# CYAN_EVSE_Logic_board_v1_1.net
KiCad netlist of a schematic drawn in Altium Designer
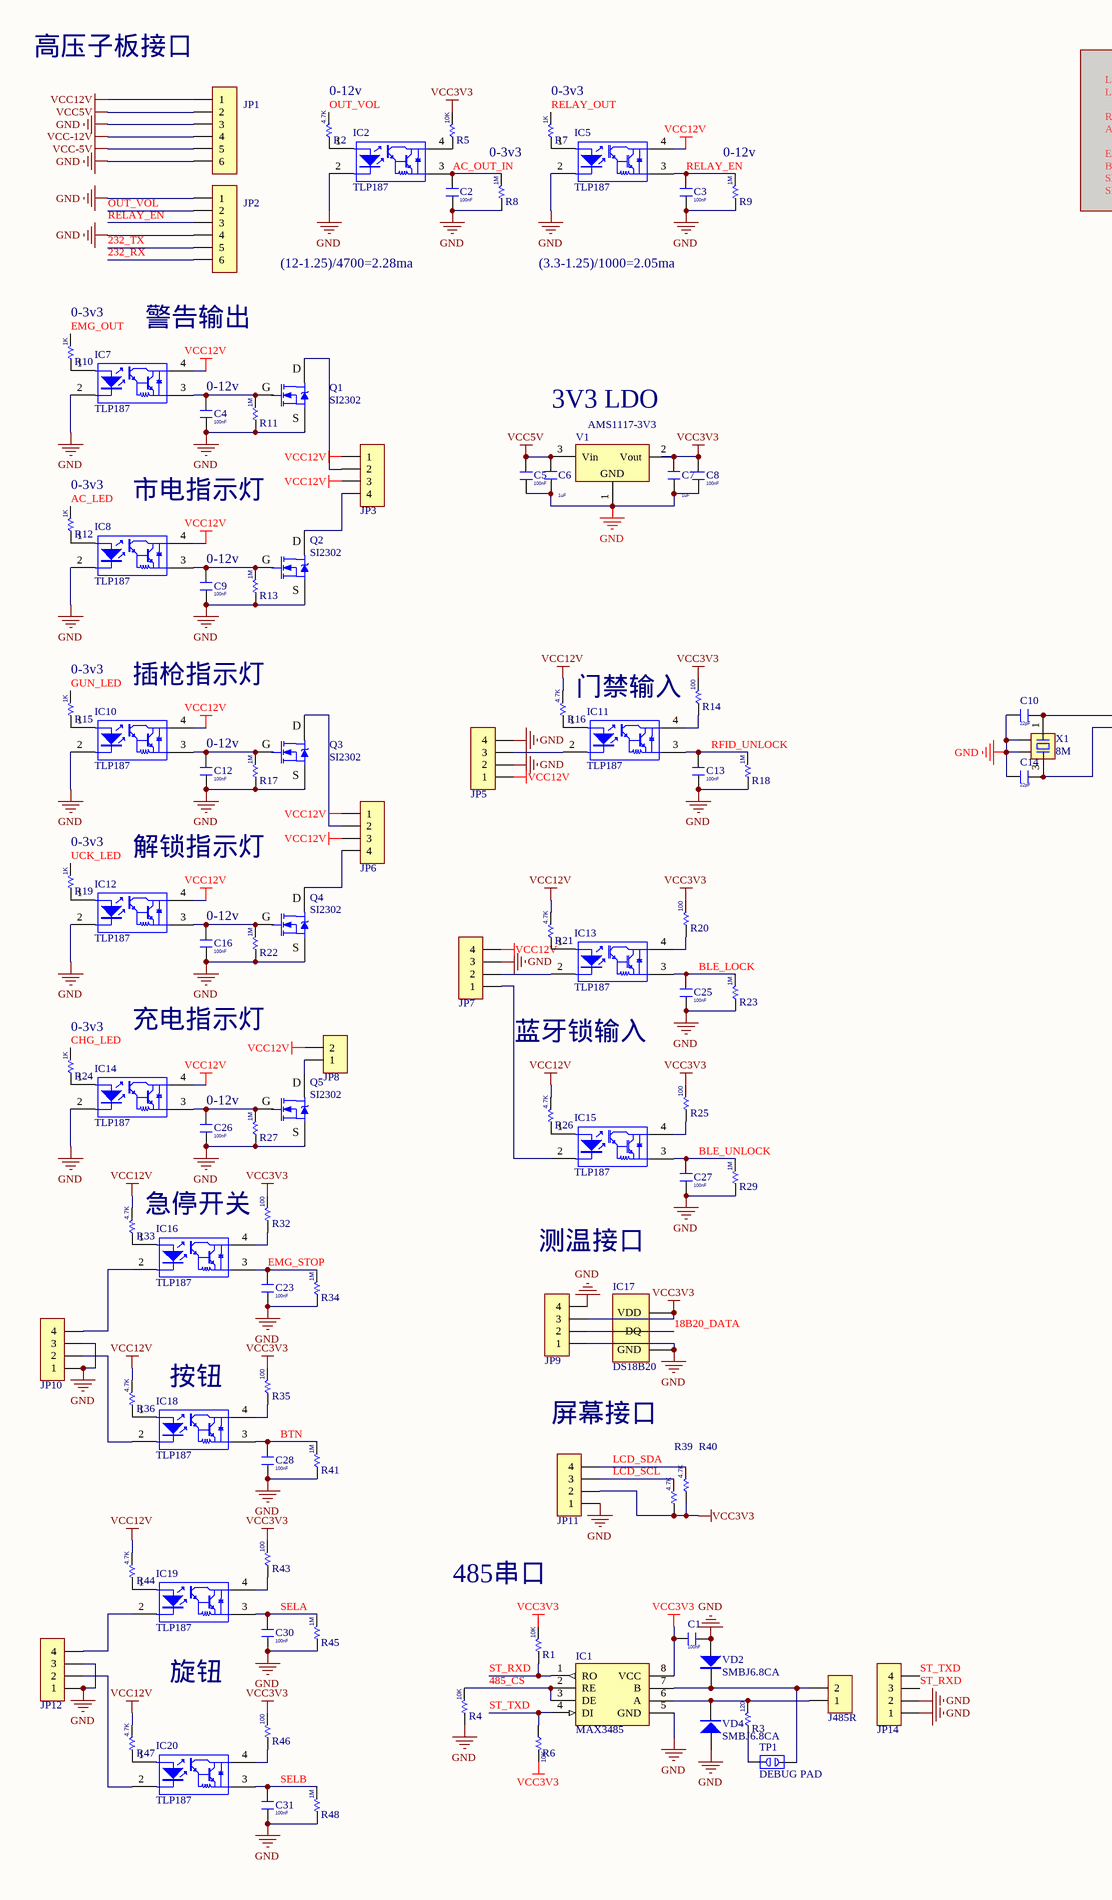
[diagram p0: CYAN_EVSE_Logic_board_v1.1.SchDoc, left]
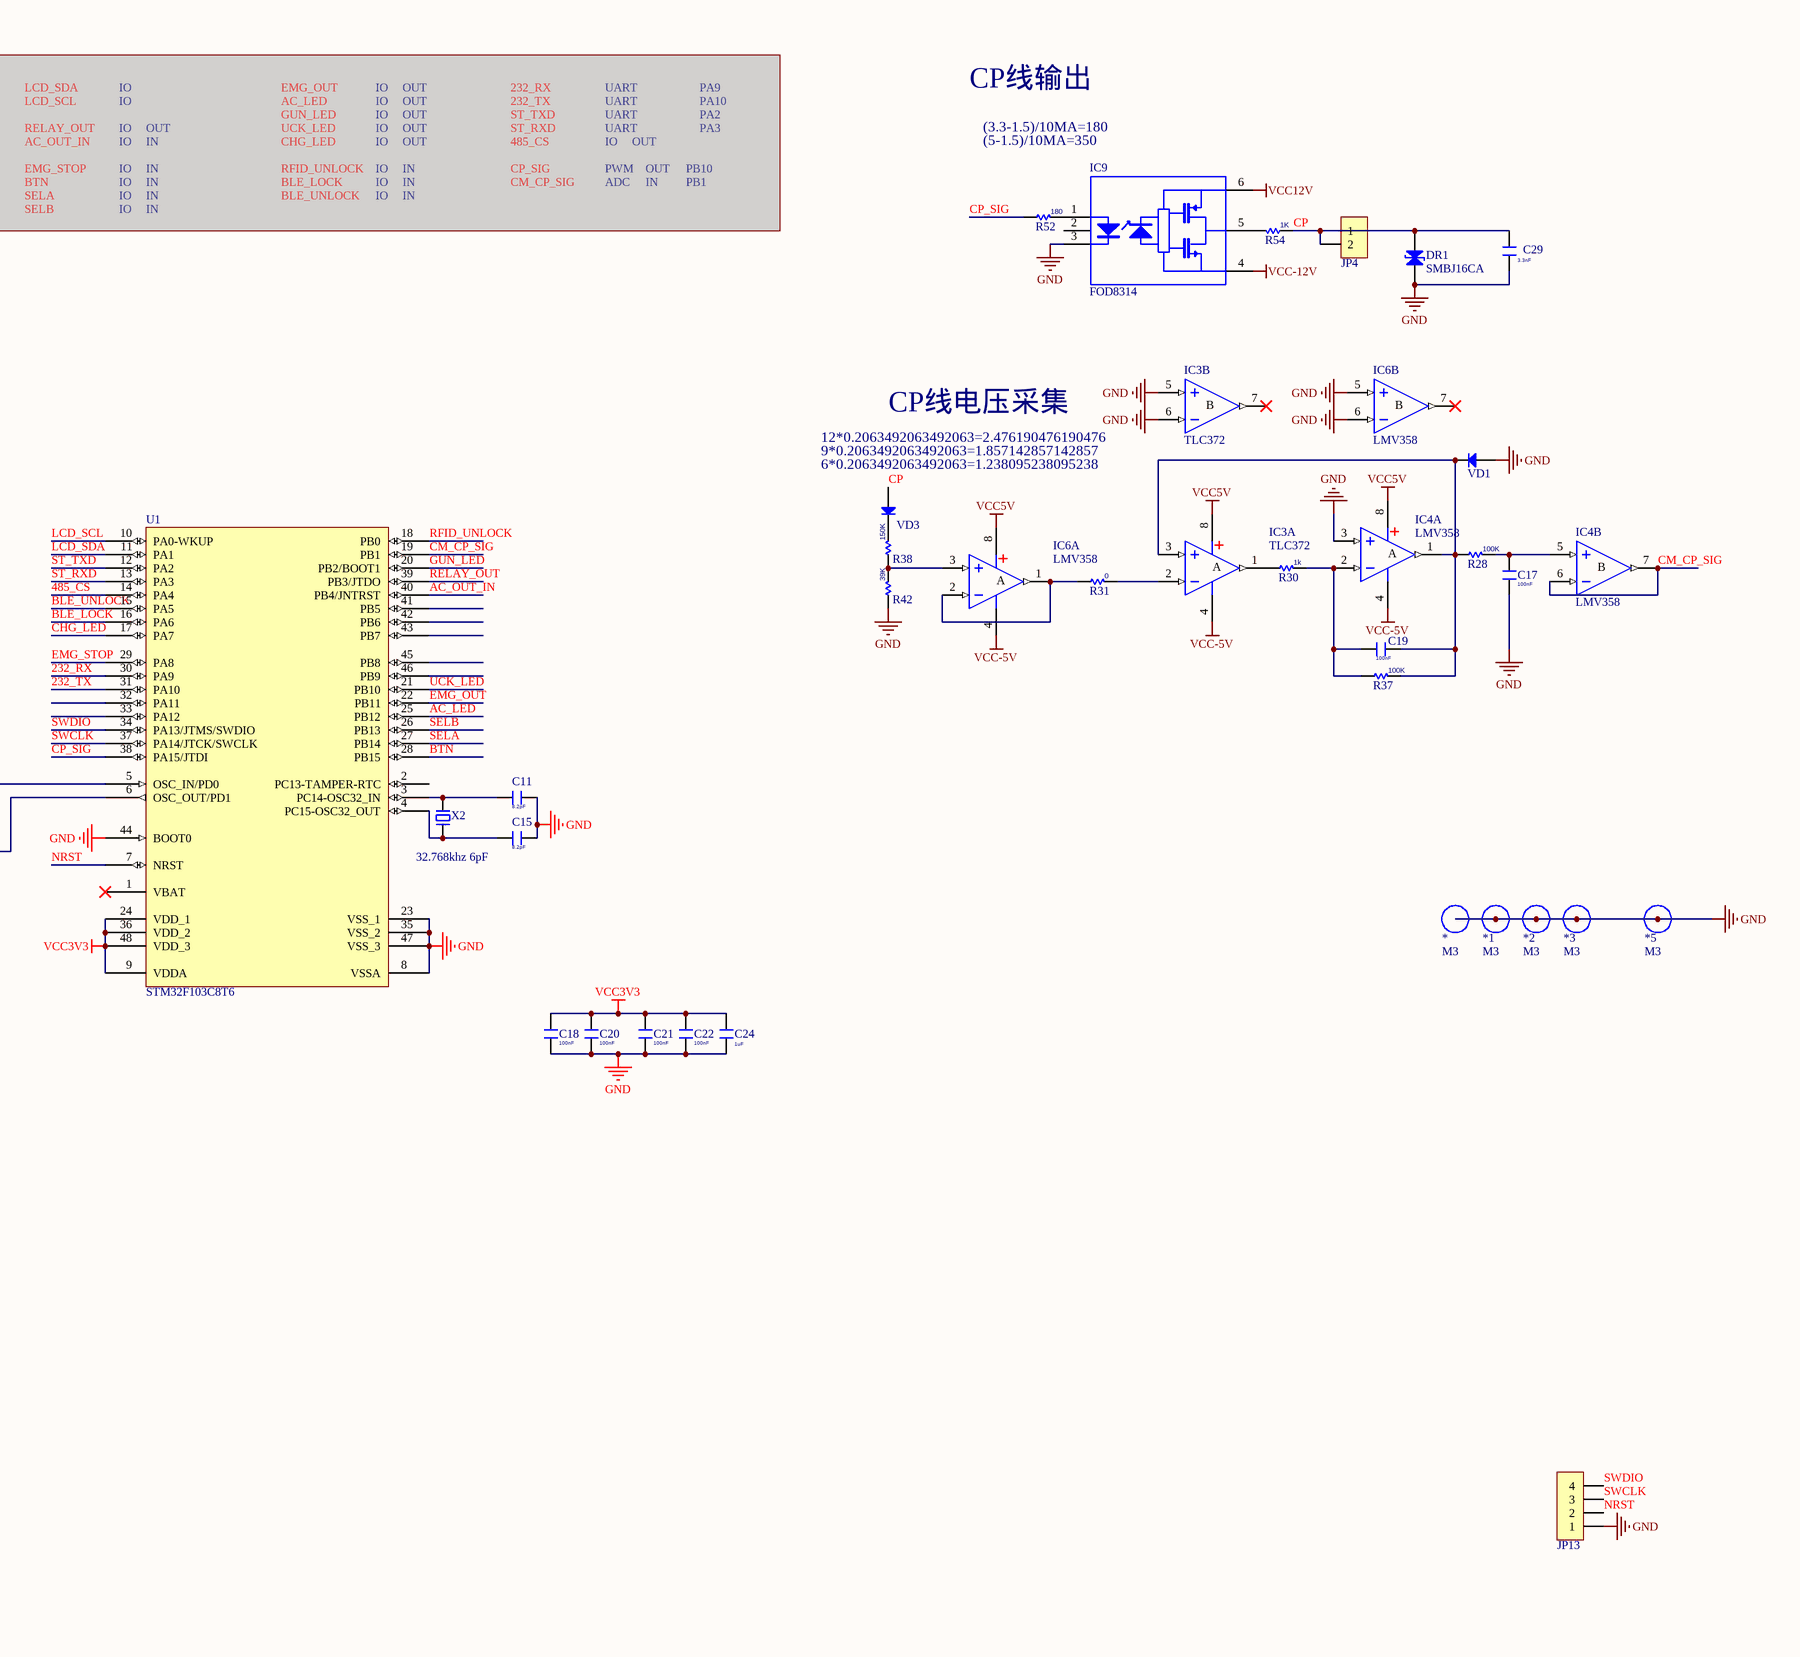
[diagram p1: CYAN_EVSE_Logic_board_v1.1.SchDoc, right]

(export (version "E")
  (design (tool "Eeschema 10.0.6"))
  (components
    (comp (ref "*")
      (value "M3")
      (footprint "M3 125X300")
      (description "铜柱孔")
      (libsource (lib "未分类器件") (part "M3"))
    )
    (comp (ref "*1")
      (value "M3")
      (footprint "M3 125X300")
      (description "铜柱孔")
      (libsource (lib "未分类器件") (part "M3"))
    )
    (comp (ref "*2")
      (value "M3")
      (footprint "M3 125X300")
      (description "铜柱孔")
      (libsource (lib "未分类器件") (part "M3"))
    )
    (comp (ref "*3")
      (value "M3")
      (footprint "M3 125X300")
      (description "铜柱孔")
      (libsource (lib "未分类器件") (part "M3"))
    )
    (comp (ref "*5")
      (value "M3")
      (footprint "M3 125X300")
      (description "铜柱孔")
      (libsource (lib "未分类器件") (part "M3"))
    )
    (comp (ref "C1")
      (value "100nF")
      (footprint "C 0805")
      (description "无极性贴片电容")
      (fields (field (name "VOLTAGE") "20V") (field (name "Comment") "C"))
      (libsource (lib "电阻-电容-电感") (part "C"))
    )
    (comp (ref "C2")
      (value "100nF")
      (footprint "C 0805")
      (description "无极性贴片电容")
      (fields (field (name "VOLTAGE") "20V") (field (name "Comment") "C"))
      (libsource (lib "电阻-电容-电感") (part "C"))
    )
    (comp (ref "C3")
      (value "100nF")
      (footprint "C 0805")
      (description "无极性贴片电容")
      (fields (field (name "VOLTAGE") "20V") (field (name "Comment") "C"))
      (libsource (lib "电阻-电容-电感") (part "C"))
    )
    (comp (ref "C4")
      (value "100nF")
      (footprint "C 0805")
      (description "无极性贴片电容")
      (fields (field (name "VOLTAGE") "20V") (field (name "Comment") "C"))
      (libsource (lib "电阻-电容-电感") (part "C"))
    )
    (comp (ref "C5")
      (value "100nF")
      (footprint "C 0805")
      (description "无极性贴片电容")
      (fields (field (name "VOLTAGE") "20V") (field (name "Comment") "C"))
      (libsource (lib "电阻-电容-电感") (part "C"))
    )
    (comp (ref "C6")
      (value "1uF")
      (footprint "C 0805")
      (description "无极性贴片电容")
      (fields (field (name "Comment") "C"))
      (libsource (lib "电阻-电容-电感") (part "C"))
    )
    (comp (ref "C7")
      (value "1uF")
      (footprint "C 0805")
      (description "无极性贴片电容")
      (fields (field (name "Comment") "C"))
      (libsource (lib "电阻-电容-电感") (part "C"))
    )
    (comp (ref "C8")
      (value "100nF")
      (footprint "C 0805")
      (description "无极性贴片电容")
      (fields (field (name "VOLTAGE") "20V") (field (name "Comment") "C"))
      (libsource (lib "电阻-电容-电感") (part "C"))
    )
    (comp (ref "C9")
      (value "100nF")
      (footprint "C 0805")
      (description "无极性贴片电容")
      (fields (field (name "VOLTAGE") "20V") (field (name "Comment") "C"))
      (libsource (lib "电阻-电容-电感") (part "C"))
    )
    (comp (ref "C10")
      (value "22pF")
      (footprint "C 0805")
      (description "无极性贴片电容")
      (fields (field (name "VOLTAGE") "20V") (field (name "Comment") "C"))
      (libsource (lib "电阻-电容-电感") (part "C"))
    )
    (comp (ref "C11")
      (value "8.2pF")
      (footprint "C 0805")
      (description "无极性贴片电容")
      (fields (field (name "VOLTAGE") "20V") (field (name "Comment") "C"))
      (libsource (lib "电阻-电容-电感") (part "C"))
    )
    (comp (ref "C12")
      (value "100nF")
      (footprint "C 0805")
      (description "无极性贴片电容")
      (fields (field (name "VOLTAGE") "20V") (field (name "Comment") "C"))
      (libsource (lib "电阻-电容-电感") (part "C"))
    )
    (comp (ref "C13")
      (value "100nF")
      (footprint "C 0805")
      (description "无极性贴片电容")
      (fields (field (name "VOLTAGE") "20V") (field (name "Comment") "C"))
      (libsource (lib "电阻-电容-电感") (part "C"))
    )
    (comp (ref "C14")
      (value "22pF")
      (footprint "C 0805")
      (description "无极性贴片电容")
      (fields (field (name "VOLTAGE") "20V") (field (name "Comment") "C"))
      (libsource (lib "电阻-电容-电感") (part "C"))
    )
    (comp (ref "C15")
      (value "8.2pF")
      (footprint "C 0805")
      (description "无极性贴片电容")
      (fields (field (name "VOLTAGE") "20V") (field (name "Comment") "C"))
      (libsource (lib "电阻-电容-电感") (part "C"))
    )
    (comp (ref "C16")
      (value "100nF")
      (footprint "C 0805")
      (description "无极性贴片电容")
      (fields (field (name "VOLTAGE") "20V") (field (name "Comment") "C"))
      (libsource (lib "电阻-电容-电感") (part "C"))
    )
    (comp (ref "C17")
      (value "100nF")
      (footprint "C 0805")
      (description "无极性贴片电容")
      (fields (field (name "VOLTAGE") "20V") (field (name "Comment") "C"))
      (libsource (lib "电阻-电容-电感") (part "C"))
    )
    (comp (ref "C18")
      (value "100nF")
      (footprint "C 0805")
      (description "无极性贴片电容")
      (fields (field (name "VOLTAGE") "20V") (field (name "Comment") "C"))
      (libsource (lib "电阻-电容-电感") (part "C"))
    )
    (comp (ref "C19")
      (value "100nF")
      (footprint "C 0805")
      (description "无极性贴片电容")
      (fields (field (name "VOLTAGE") "20V") (field (name "Comment") "C"))
      (libsource (lib "电阻-电容-电感") (part "C"))
    )
    (comp (ref "C20")
      (value "100nF")
      (footprint "C 0805")
      (description "无极性贴片电容")
      (fields (field (name "VOLTAGE") "20V") (field (name "Comment") "C"))
      (libsource (lib "电阻-电容-电感") (part "C"))
    )
    (comp (ref "C21")
      (value "100nF")
      (footprint "C 0805")
      (description "无极性贴片电容")
      (fields (field (name "VOLTAGE") "20V") (field (name "Comment") "C"))
      (libsource (lib "电阻-电容-电感") (part "C"))
    )
    (comp (ref "C22")
      (value "100nF")
      (footprint "C 0805")
      (description "无极性贴片电容")
      (fields (field (name "VOLTAGE") "20V") (field (name "Comment") "C"))
      (libsource (lib "电阻-电容-电感") (part "C"))
    )
    (comp (ref "C23")
      (value "100nF")
      (footprint "C 0805")
      (description "无极性贴片电容")
      (fields (field (name "VOLTAGE") "20V") (field (name "Comment") "C"))
      (libsource (lib "电阻-电容-电感") (part "C"))
    )
    (comp (ref "C24")
      (value "1uF")
      (footprint "C 0805")
      (description "无极性贴片电容")
      (fields (field (name "Comment") "C"))
      (libsource (lib "电阻-电容-电感") (part "C"))
    )
    (comp (ref "C25")
      (value "100nF")
      (footprint "C 0805")
      (description "无极性贴片电容")
      (fields (field (name "VOLTAGE") "20V") (field (name "Comment") "C"))
      (libsource (lib "电阻-电容-电感") (part "C"))
    )
    (comp (ref "C26")
      (value "100nF")
      (footprint "C 0805")
      (description "无极性贴片电容")
      (fields (field (name "VOLTAGE") "20V") (field (name "Comment") "C"))
      (libsource (lib "电阻-电容-电感") (part "C"))
    )
    (comp (ref "C27")
      (value "100nF")
      (footprint "C 0805")
      (description "无极性贴片电容")
      (fields (field (name "VOLTAGE") "20V") (field (name "Comment") "C"))
      (libsource (lib "电阻-电容-电感") (part "C"))
    )
    (comp (ref "C28")
      (value "100nF")
      (footprint "C 0805")
      (description "无极性贴片电容")
      (fields (field (name "VOLTAGE") "20V") (field (name "Comment") "C"))
      (libsource (lib "电阻-电容-电感") (part "C"))
    )
    (comp (ref "C29")
      (value "3.3nF")
      (footprint "C 1206")
      (description "无极性贴片电容")
      (fields (field (name "VOLTAGE") "50V") (field (name "Comment") "C"))
      (libsource (lib "电阻-电容-电感") (part "C"))
    )
    (comp (ref "C30")
      (value "100nF")
      (footprint "C 0805")
      (description "无极性贴片电容")
      (fields (field (name "VOLTAGE") "20V") (field (name "Comment") "C"))
      (libsource (lib "电阻-电容-电感") (part "C"))
    )
    (comp (ref "C31")
      (value "100nF")
      (footprint "C 0805")
      (description "无极性贴片电容")
      (fields (field (name "VOLTAGE") "20V") (field (name "Comment") "C"))
      (libsource (lib "电阻-电容-电感") (part "C"))
    )
    (comp (ref "DR1")
      (value "SMBJ16CA")
      (footprint "SMB")
      (description "瞬态电压抑制二极管")
      (libsource (lib "二极管-整流桥") (part "DR"))
    )
    (comp (ref "IC1")
      (value "MAX3485")
      (footprint "SOP8_N")
      (description "RS485总线收发芯片")
      (libsource (lib "IC芯片") (part "MAX487"))
    )
    (comp (ref "IC2")
      (value "TLP187")
      (footprint "SOP6_4.6MM_W1.27_4PIN_N")
      (description "达林顿输出光耦")
      (libsource (lib "传感元件") (part "TLP187"))
    )
    (comp (ref "IC3")
      (value "TLC372")
      (footprint "SOP8_N")
      (description "双路电压比较,MOS下臂输出")
      (libsource (lib "IC芯片") (part "TLC372"))
    )
    (comp (ref "IC4")
      (value "LMV358")
      (footprint "SOP8_N")
      (description "双路运放")
      (libsource (lib "IC芯片") (part "LM358"))
    )
    (comp (ref "IC5")
      (value "TLP187")
      (footprint "SOP6_4.6MM_W1.27_4PIN_N")
      (description "达林顿输出光耦")
      (libsource (lib "传感元件") (part "TLP187"))
    )
    (comp (ref "IC6")
      (value "LMV358")
      (footprint "SOP8_N")
      (description "双路运放")
      (libsource (lib "IC芯片") (part "LM358"))
    )
    (comp (ref "IC7")
      (value "TLP187")
      (footprint "SOP6_4.6MM_W1.27_4PIN_N")
      (description "达林顿输出光耦")
      (libsource (lib "传感元件") (part "TLP187"))
    )
    (comp (ref "IC8")
      (value "TLP187")
      (footprint "SOP6_4.6MM_W1.27_4PIN_N")
      (description "达林顿输出光耦")
      (libsource (lib "传感元件") (part "TLP187"))
    )
    (comp (ref "IC9")
      (value "FOD8314")
      (footprint "SOP6_7MM_WIDE_LEAD_N")
      (description "MOSFET/IGBT 驱动光耦，15-30v 1a")
      (libsource (lib "传感元件") (part "FOD8314"))
    )
    (comp (ref "IC10")
      (value "TLP187")
      (footprint "SOP6_4.6MM_W1.27_4PIN_N")
      (description "达林顿输出光耦")
      (libsource (lib "传感元件") (part "TLP187"))
    )
    (comp (ref "IC11")
      (value "TLP187")
      (footprint "SOP6_4.6MM_W1.27_4PIN_N")
      (description "达林顿输出光耦")
      (libsource (lib "传感元件") (part "TLP187"))
    )
    (comp (ref "IC12")
      (value "TLP187")
      (footprint "SOP6_4.6MM_W1.27_4PIN_N")
      (description "达林顿输出光耦")
      (libsource (lib "传感元件") (part "TLP187"))
    )
    (comp (ref "IC13")
      (value "TLP187")
      (footprint "SOP6_4.6MM_W1.27_4PIN_N")
      (description "达林顿输出光耦")
      (libsource (lib "传感元件") (part "TLP187"))
    )
    (comp (ref "IC14")
      (value "TLP187")
      (footprint "SOP6_4.6MM_W1.27_4PIN_N")
      (description "达林顿输出光耦")
      (libsource (lib "传感元件") (part "TLP187"))
    )
    (comp (ref "IC15")
      (value "TLP187")
      (footprint "SOP6_4.6MM_W1.27_4PIN_N")
      (description "达林顿输出光耦")
      (libsource (lib "传感元件") (part "TLP187"))
    )
    (comp (ref "IC16")
      (value "TLP187")
      (footprint "SOP6_4.6MM_W1.27_4PIN_N")
      (description "达林顿输出光耦")
      (libsource (lib "传感元件") (part "TLP187"))
    )
    (comp (ref "IC17")
      (value "DS18B20")
      (footprint "TO92A")
      (description "数字温度计")
      (libsource (lib "IC芯片") (part "DS18B20"))
    )
    (comp (ref "IC18")
      (value "TLP187")
      (footprint "SOP6_4.6MM_W1.27_4PIN_N")
      (description "达林顿输出光耦")
      (libsource (lib "传感元件") (part "TLP187"))
    )
    (comp (ref "IC19")
      (value "TLP187")
      (footprint "SOP6_4.6MM_W1.27_4PIN_N")
      (description "达林顿输出光耦")
      (libsource (lib "传感元件") (part "TLP187"))
    )
    (comp (ref "IC20")
      (value "TLP187")
      (footprint "SOP6_4.6MM_W1.27_4PIN_N")
      (description "达林顿输出光耦")
      (libsource (lib "传感元件") (part "TLP187"))
    )
    (comp (ref "J485R")
      (value "HDR-1X2")
      (footprint "MC 1,5/ 2-G-3,81")
      (description "2P接插件")
      (libsource (lib "接插件") (part "Header 2"))
    )
    (comp (ref "JP1")
      (value "HDR-1X6")
      (footprint "XH2.54-6P")
      (description "6P接插件")
      (libsource (lib "接插件") (part "Header 6"))
    )
    (comp (ref "JP2")
      (value "HDR-1X6")
      (footprint "XH2.54-6P")
      (description "6P接插件")
      (libsource (lib "接插件") (part "Header 6"))
    )
    (comp (ref "JP3")
      (value "HDR-1X4")
      (footprint "MC 1,5/ 4-G-3,81")
      (description "4P接插件")
      (libsource (lib "") (part "Header 4_1"))
    )
    (comp (ref "JP4")
      (value "HDR-1X2")
      (footprint "MC 1,5/ 2-G-3,81")
      (description "2P接插件")
      (libsource (lib "") (part "Header 2_1"))
    )
    (comp (ref "JP5")
      (value "HDR-1X4")
      (footprint "MC 1,5/ 4-G-3,81")
      (description "4P接插件")
      (libsource (lib "接插件") (part "Header 4"))
    )
    (comp (ref "JP6")
      (value "HDR-1X4")
      (footprint "MC 1,5/ 4-G-3,81")
      (description "4P接插件")
      (libsource (lib "") (part "Header 4_1"))
    )
    (comp (ref "JP7")
      (value "HDR-1X4")
      (footprint "MC 1,5/ 4-G-3,81")
      (description "4P接插件")
      (libsource (lib "接插件") (part "Header 4"))
    )
    (comp (ref "JP8")
      (value "HDR-1X2")
      (footprint "MC 1,5/ 2-G-3,81")
      (description "2P接插件")
      (libsource (lib "接插件") (part "Header 2"))
    )
    (comp (ref "JP9")
      (value "HDR-1X4")
      (footprint "MC 1,5/ 4-G-3,81")
      (description "4P接插件")
      (libsource (lib "接插件") (part "Header 4"))
    )
    (comp (ref "JP10")
      (value "HDR-1X4")
      (footprint "MC 1,5/ 4-G-3,81")
      (description "4P接插件")
      (libsource (lib "接插件") (part "Header 4"))
    )
    (comp (ref "JP11")
      (value "HDR-1X4")
      (footprint "XH2.54-4P")
      (description "4P接插件")
      (libsource (lib "接插件") (part "Header 4"))
    )
    (comp (ref "JP12")
      (value "HDR-1X4")
      (footprint "MC 1,5/ 4-G-3,81")
      (description "4P接插件")
      (libsource (lib "接插件") (part "Header 4"))
    )
    (comp (ref "JP13")
      (value "HDR-1X4")
      (footprint "HDR-1X4")
      (description "4P接插件")
      (libsource (lib "接插件") (part "Header 4"))
    )
    (comp (ref "JP14")
      (value "HDR-1X4")
      (footprint "HDR-1X4")
      (description "4P接插件")
      (libsource (lib "接插件") (part "Header 4"))
    )
    (comp (ref "Q1")
      (value "SI2302")
      (footprint "SOT23-3N")
      (description "N沟道场效应管")
      (libsource (lib "场效应管-可控硅") (part "SI2302"))
    )
    (comp (ref "Q2")
      (value "SI2302")
      (footprint "SOT23-3N")
      (description "N沟道场效应管")
      (libsource (lib "场效应管-可控硅") (part "SI2302"))
    )
    (comp (ref "Q3")
      (value "SI2302")
      (footprint "SOT23-3N")
      (description "N沟道场效应管")
      (libsource (lib "场效应管-可控硅") (part "SI2302"))
    )
    (comp (ref "Q4")
      (value "SI2302")
      (footprint "SOT23-3N")
      (description "N沟道场效应管")
      (libsource (lib "场效应管-可控硅") (part "SI2302"))
    )
    (comp (ref "Q5")
      (value "SI2302")
      (footprint "SOT23-3N")
      (description "N沟道场效应管")
      (libsource (lib "场效应管-可控硅") (part "SI2302"))
    )
    (comp (ref "R1")
      (value "10K")
      (footprint "R 0805")
      (description "贴片电阻")
      (fields (field (name "Comment") "R"))
      (libsource (lib "电阻-电容-电感") (part "R"))
    )
    (comp (ref "R2")
      (value "4.7K")
      (footprint "R 0805")
      (description "贴片电阻")
      (fields (field (name "Comment") "R"))
      (libsource (lib "电阻-电容-电感") (part "R"))
    )
    (comp (ref "R3")
      (value "120")
      (footprint "R 1206")
      (description "贴片电阻")
      (fields (field (name "Comment") "R"))
      (libsource (lib "电阻-电容-电感") (part "R"))
    )
    (comp (ref "R4")
      (value "10K")
      (footprint "R 0805")
      (description "贴片电阻")
      (fields (field (name "Comment") "R"))
      (libsource (lib "电阻-电容-电感") (part "R"))
    )
    (comp (ref "R5")
      (value "10K")
      (footprint "R 0805")
      (description "贴片电阻")
      (fields (field (name "Comment") "R"))
      (libsource (lib "电阻-电容-电感") (part "R"))
    )
    (comp (ref "R6")
      (value "10K")
      (footprint "R 0805")
      (description "贴片电阻")
      (fields (field (name "Comment") "R"))
      (libsource (lib "电阻-电容-电感") (part "R"))
    )
    (comp (ref "R7")
      (value "1K")
      (footprint "R 0805")
      (description "贴片电阻")
      (fields (field (name "Comment") "R"))
      (libsource (lib "电阻-电容-电感") (part "R"))
    )
    (comp (ref "R8")
      (value "1M")
      (footprint "R 0805")
      (description "贴片电阻")
      (fields (field (name "Comment") "R"))
      (libsource (lib "电阻-电容-电感") (part "R"))
    )
    (comp (ref "R9")
      (value "1M")
      (footprint "R 0805")
      (description "贴片电阻")
      (fields (field (name "Comment") "R"))
      (libsource (lib "电阻-电容-电感") (part "R"))
    )
    (comp (ref "R10")
      (value "1K")
      (footprint "R 0805")
      (description "贴片电阻")
      (fields (field (name "Comment") "R"))
      (libsource (lib "电阻-电容-电感") (part "R"))
    )
    (comp (ref "R11")
      (value "1M")
      (footprint "R 0805")
      (description "贴片电阻")
      (fields (field (name "Comment") "R"))
      (libsource (lib "电阻-电容-电感") (part "R"))
    )
    (comp (ref "R12")
      (value "1K")
      (footprint "R 0805")
      (description "贴片电阻")
      (fields (field (name "Comment") "R"))
      (libsource (lib "电阻-电容-电感") (part "R"))
    )
    (comp (ref "R13")
      (value "1M")
      (footprint "R 0805")
      (description "贴片电阻")
      (fields (field (name "Comment") "R"))
      (libsource (lib "电阻-电容-电感") (part "R"))
    )
    (comp (ref "R14")
      (value "100")
      (footprint "R 0805")
      (description "贴片电阻")
      (fields (field (name "Comment") "R"))
      (libsource (lib "电阻-电容-电感") (part "R"))
    )
    (comp (ref "R15")
      (value "1K")
      (footprint "R 0805")
      (description "贴片电阻")
      (fields (field (name "Comment") "R"))
      (libsource (lib "电阻-电容-电感") (part "R"))
    )
    (comp (ref "R16")
      (value "4.7K")
      (footprint "R 0805")
      (description "贴片电阻")
      (fields (field (name "Comment") "R"))
      (libsource (lib "电阻-电容-电感") (part "R"))
    )
    (comp (ref "R17")
      (value "1M")
      (footprint "R 0805")
      (description "贴片电阻")
      (fields (field (name "Comment") "R"))
      (libsource (lib "电阻-电容-电感") (part "R"))
    )
    (comp (ref "R18")
      (value "1M")
      (footprint "R 0805")
      (description "贴片电阻")
      (fields (field (name "Comment") "R"))
      (libsource (lib "电阻-电容-电感") (part "R"))
    )
    (comp (ref "R19")
      (value "1K")
      (footprint "R 0805")
      (description "贴片电阻")
      (fields (field (name "Comment") "R"))
      (libsource (lib "电阻-电容-电感") (part "R"))
    )
    (comp (ref "R20")
      (value "100")
      (footprint "R 0805")
      (description "贴片电阻")
      (fields (field (name "Comment") "R"))
      (libsource (lib "电阻-电容-电感") (part "R"))
    )
    (comp (ref "R21")
      (value "4.7K")
      (footprint "R 0805")
      (description "贴片电阻")
      (fields (field (name "Comment") "R"))
      (libsource (lib "电阻-电容-电感") (part "R"))
    )
    (comp (ref "R22")
      (value "1M")
      (footprint "R 0805")
      (description "贴片电阻")
      (fields (field (name "Comment") "R"))
      (libsource (lib "电阻-电容-电感") (part "R"))
    )
    (comp (ref "R23")
      (value "1M")
      (footprint "R 0805")
      (description "贴片电阻")
      (fields (field (name "Comment") "R"))
      (libsource (lib "电阻-电容-电感") (part "R"))
    )
    (comp (ref "R24")
      (value "1K")
      (footprint "R 0805")
      (description "贴片电阻")
      (fields (field (name "Comment") "R"))
      (libsource (lib "电阻-电容-电感") (part "R"))
    )
    (comp (ref "R25")
      (value "100")
      (footprint "R 0805")
      (description "贴片电阻")
      (fields (field (name "Comment") "R"))
      (libsource (lib "电阻-电容-电感") (part "R"))
    )
    (comp (ref "R26")
      (value "4.7K")
      (footprint "R 0805")
      (description "贴片电阻")
      (fields (field (name "Comment") "R"))
      (libsource (lib "电阻-电容-电感") (part "R"))
    )
    (comp (ref "R27")
      (value "1M")
      (footprint "R 0805")
      (description "贴片电阻")
      (fields (field (name "Comment") "R"))
      (libsource (lib "电阻-电容-电感") (part "R"))
    )
    (comp (ref "R28")
      (value "100K")
      (footprint "R 0805")
      (description "贴片电阻")
      (fields (field (name "Comment") "R"))
      (libsource (lib "电阻-电容-电感") (part "R"))
    )
    (comp (ref "R29")
      (value "1M")
      (footprint "R 0805")
      (description "贴片电阻")
      (fields (field (name "Comment") "R"))
      (libsource (lib "电阻-电容-电感") (part "R"))
    )
    (comp (ref "R30")
      (value "1k")
      (footprint "R 0805")
      (description "贴片电阻")
      (fields (field (name "Comment") "R"))
      (libsource (lib "电阻-电容-电感") (part "R"))
    )
    (comp (ref "R31")
      (value "0")
      (footprint "R 0805")
      (description "贴片电阻")
      (fields (field (name "Comment") "R"))
      (libsource (lib "电阻-电容-电感") (part "R"))
    )
    (comp (ref "R32")
      (value "100")
      (footprint "R 0805")
      (description "贴片电阻")
      (fields (field (name "Comment") "R"))
      (libsource (lib "电阻-电容-电感") (part "R"))
    )
    (comp (ref "R33")
      (value "4.7K")
      (footprint "R 0805")
      (description "贴片电阻")
      (fields (field (name "Comment") "R"))
      (libsource (lib "电阻-电容-电感") (part "R"))
    )
    (comp (ref "R34")
      (value "1M")
      (footprint "R 0805")
      (description "贴片电阻")
      (fields (field (name "Comment") "R"))
      (libsource (lib "电阻-电容-电感") (part "R"))
    )
    (comp (ref "R35")
      (value "100")
      (footprint "R 0805")
      (description "贴片电阻")
      (fields (field (name "Comment") "R"))
      (libsource (lib "电阻-电容-电感") (part "R"))
    )
    (comp (ref "R36")
      (value "4.7K")
      (footprint "R 0805")
      (description "贴片电阻")
      (fields (field (name "Comment") "R"))
      (libsource (lib "电阻-电容-电感") (part "R"))
    )
    (comp (ref "R37")
      (value "100K")
      (footprint "R 0805")
      (description "贴片电阻")
      (fields (field (name "Comment") "R"))
      (libsource (lib "电阻-电容-电感") (part "R"))
    )
    (comp (ref "R38")
      (value "150K")
      (footprint "R 0805")
      (description "贴片电阻")
      (fields (field (name "Comment") "R"))
      (libsource (lib "电阻-电容-电感") (part "R"))
    )
    (comp (ref "R39")
      (value "4.7K")
      (footprint "R 0805")
      (description "贴片电阻")
      (fields (field (name "Comment") "R"))
      (libsource (lib "电阻-电容-电感") (part "R"))
    )
    (comp (ref "R40")
      (value "4.7K")
      (footprint "R 0805")
      (description "贴片电阻")
      (fields (field (name "Comment") "R"))
      (libsource (lib "电阻-电容-电感") (part "R"))
    )
    (comp (ref "R41")
      (value "1M")
      (footprint "R 0805")
      (description "贴片电阻")
      (fields (field (name "Comment") "R"))
      (libsource (lib "电阻-电容-电感") (part "R"))
    )
    (comp (ref "R42")
      (value "39K")
      (footprint "R 0805")
      (description "贴片电阻")
      (fields (field (name "Comment") "R"))
      (libsource (lib "电阻-电容-电感") (part "R"))
    )
    (comp (ref "R43")
      (value "100")
      (footprint "R 0805")
      (description "贴片电阻")
      (fields (field (name "Comment") "R"))
      (libsource (lib "电阻-电容-电感") (part "R"))
    )
    (comp (ref "R44")
      (value "4.7K")
      (footprint "R 0805")
      (description "贴片电阻")
      (fields (field (name "Comment") "R"))
      (libsource (lib "电阻-电容-电感") (part "R"))
    )
    (comp (ref "R45")
      (value "1M")
      (footprint "R 0805")
      (description "贴片电阻")
      (fields (field (name "Comment") "R"))
      (libsource (lib "电阻-电容-电感") (part "R"))
    )
    (comp (ref "R46")
      (value "100")
      (footprint "R 0805")
      (description "贴片电阻")
      (fields (field (name "Comment") "R"))
      (libsource (lib "电阻-电容-电感") (part "R"))
    )
    (comp (ref "R47")
      (value "4.7K")
      (footprint "R 0805")
      (description "贴片电阻")
      (fields (field (name "Comment") "R"))
      (libsource (lib "电阻-电容-电感") (part "R"))
    )
    (comp (ref "R48")
      (value "1M")
      (footprint "R 0805")
      (description "贴片电阻")
      (fields (field (name "Comment") "R"))
      (libsource (lib "电阻-电容-电感") (part "R"))
    )
    (comp (ref "R52")
      (value "180")
      (footprint "R 0805")
      (description "贴片电阻")
      (fields (field (name "Comment") "R"))
      (libsource (lib "电阻-电容-电感") (part "R"))
    )
    (comp (ref "R54")
      (value "1K")
      (footprint "R 1206")
      (description "贴片电阻")
      (fields (field (name "Comment") "R"))
      (libsource (lib "电阻-电容-电感") (part "R"))
    )
    (comp (ref "TP1")
      (value "DEBUG PAD")
      (footprint "DEBUG PAD2")
      (description "调试断点焊盘")
      (libsource (lib "未分类器件") (part "DEBUG"))
    )
    (comp (ref "U1")
      (value "STM32F103C8T6")
      (footprint "LQFP48 7X7_M")
      (description "Flaah:64/RAM:20/IO:36")
      (libsource (lib "STM32系列单片机") (part "STM32F103C8T6"))
    )
    (comp (ref "V1")
      (value "AMS1117-3V3")
      (footprint "SOT223_L")
      (description "三端稳压芯片")
      (libsource (lib "IC芯片") (part "AMS1117"))
    )
    (comp (ref "VD1")
      (value "1N4148")
      (footprint "SOD-323")
      (description "高速开关二极管")
      (libsource (lib "二极管-整流桥") (part "1N4148"))
    )
    (comp (ref "VD2")
      (value "SMBJ6.8CA")
      (footprint "SMB")
      (description "肖特基二极管")
      (libsource (lib "二极管-整流桥") (part "SS14"))
    )
    (comp (ref "VD3")
      (value "1N4148")
      (footprint "SOD-323")
      (description "高速开关二极管")
      (libsource (lib "二极管-整流桥") (part "1N4148"))
    )
    (comp (ref "VD4")
      (value "SMBJ6.8CA")
      (footprint "SMB")
      (description "肖特基二极管")
      (libsource (lib "二极管-整流桥") (part "SS14"))
    )
    (comp (ref "X1")
      (value "8M")
      (footprint "XTAL-3225")
      (description "4脚晶振")
      (libsource (lib "保险丝-晶振") (part "XTAL-4"))
    )
    (comp (ref "X2")
      (value "32.768khz 6pF")
      (footprint "XTAL-3215")
      (description "2脚晶振")
      (libsource (lib "保险丝-晶振") (part "XTAL-2"))
    )
  )
  (nets
    (net (code "1") (name "/18B20_DATA") (class "Default")
      (node (ref "IC17") (pin "2") (pinfunction "DQ_2") (pintype "passive"))
      (node (ref "JP9") (pin "2") (pinfunction "2_2") (pintype "passive"))
    )
    (net (code "2") (name "/232_RX") (class "Default")
      (node (ref "JP2") (pin "6") (pinfunction "6_6") (pintype "passive"))
      (node (ref "U1") (pin "30") (pinfunction "PA9_30") (pintype "bidirectional"))
    )
    (net (code "3") (name "/232_TX") (class "Default")
      (node (ref "JP2") (pin "5") (pinfunction "5_5") (pintype "passive"))
      (node (ref "U1") (pin "31") (pinfunction "PA10_31") (pintype "bidirectional"))
    )
    (net (code "4") (name "/485_CS") (class "Default")
      (node (ref "IC1") (pin "2") (pinfunction "RE_2") (pintype "passive"))
      (node (ref "IC1") (pin "3") (pinfunction "DE_3") (pintype "passive"))
      (node (ref "R4") (pin "2") (pinfunction "2_2") (pintype "passive"))
      (node (ref "U1") (pin "14") (pinfunction "PA4_14") (pintype "bidirectional"))
    )
    (net (code "5") (name "/AC_LED") (class "Default")
      (node (ref "R12") (pin "2") (pinfunction "2_2") (pintype "passive"))
      (node (ref "U1") (pin "25") (pinfunction "PB12_25") (pintype "bidirectional"))
    )
    (net (code "6") (name "/AC_OUT_IN") (class "Default")
      (node (ref "C2") (pin "2") (pinfunction "2_2") (pintype "passive"))
      (node (ref "IC2") (pin "3") (pinfunction "E_3") (pintype "passive"))
      (node (ref "R8") (pin "2") (pinfunction "2_2") (pintype "passive"))
      (node (ref "U1") (pin "40") (pinfunction "PB4/JNTRST_40") (pintype "bidirectional"))
    )
    (net (code "7") (name "/BLE_LOCK") (class "Default")
      (node (ref "C25") (pin "2") (pinfunction "2_2") (pintype "passive"))
      (node (ref "IC13") (pin "3") (pinfunction "E_3") (pintype "passive"))
      (node (ref "R23") (pin "2") (pinfunction "2_2") (pintype "passive"))
      (node (ref "U1") (pin "16") (pinfunction "PA6_16") (pintype "bidirectional"))
    )
    (net (code "8") (name "/BLE_UNLOCK") (class "Default")
      (node (ref "C27") (pin "2") (pinfunction "2_2") (pintype "passive"))
      (node (ref "IC15") (pin "3") (pinfunction "E_3") (pintype "passive"))
      (node (ref "R29") (pin "2") (pinfunction "2_2") (pintype "passive"))
      (node (ref "U1") (pin "15") (pinfunction "PA5_15") (pintype "bidirectional"))
    )
    (net (code "9") (name "/BTN") (class "Default")
      (node (ref "C28") (pin "2") (pinfunction "2_2") (pintype "passive"))
      (node (ref "IC18") (pin "3") (pinfunction "E_3") (pintype "passive"))
      (node (ref "R41") (pin "2") (pinfunction "2_2") (pintype "passive"))
      (node (ref "U1") (pin "28") (pinfunction "PB15_28") (pintype "bidirectional"))
    )
    (net (code "10") (name "/CHG_LED") (class "Default")
      (node (ref "R24") (pin "2") (pinfunction "2_2") (pintype "passive"))
      (node (ref "U1") (pin "17") (pinfunction "PA7_17") (pintype "bidirectional"))
    )
    (net (code "11") (name "/CM_CP_SIG") (class "Default")
      (node (ref "IC4") (pin "6") (pinfunction "IN-_6") (pintype "input"))
      (node (ref "IC4") (pin "7") (pinfunction "OUT_7") (pintype "output"))
      (node (ref "U1") (pin "19") (pinfunction "PB1_19") (pintype "bidirectional"))
    )
    (net (code "12") (name "/CP") (class "Default")
      (node (ref "C29") (pin "2") (pinfunction "2_2") (pintype "passive"))
      (node (ref "DR1") (pin "1") (pinfunction "A_1") (pintype "passive"))
      (node (ref "JP4") (pin "1") (pinfunction "1_1") (pintype "passive"))
      (node (ref "JP4") (pin "2") (pinfunction "2_2") (pintype "passive"))
      (node (ref "R54") (pin "1") (pinfunction "1_1") (pintype "passive"))
      (node (ref "VD3") (pin "1") (pinfunction "A_1") (pintype "passive"))
    )
    (net (code "13") (name "/CP_SIG") (class "Default")
      (node (ref "R52") (pin "1") (pinfunction "1_1") (pintype "passive"))
      (node (ref "U1") (pin "38") (pinfunction "PA15/JTDI_38") (pintype "bidirectional"))
    )
    (net (code "14") (name "/EMG_OUT") (class "Default")
      (node (ref "R10") (pin "2") (pinfunction "2_2") (pintype "passive"))
      (node (ref "U1") (pin "22") (pinfunction "PB11_22") (pintype "bidirectional"))
    )
    (net (code "15") (name "/EMG_STOP") (class "Default")
      (node (ref "C23") (pin "2") (pinfunction "2_2") (pintype "passive"))
      (node (ref "IC16") (pin "3") (pinfunction "E_3") (pintype "passive"))
      (node (ref "R34") (pin "2") (pinfunction "2_2") (pintype "passive"))
      (node (ref "U1") (pin "29") (pinfunction "PA8_29") (pintype "bidirectional"))
    )
    (net (code "16") (name "/GUN_LED") (class "Default")
      (node (ref "R15") (pin "2") (pinfunction "2_2") (pintype "passive"))
      (node (ref "U1") (pin "20") (pinfunction "PB2/BOOT1_20") (pintype "bidirectional"))
    )
    (net (code "17") (name "/LCD_SCL") (class "Default")
      (node (ref "JP11") (pin "3") (pinfunction "3_3") (pintype "passive"))
      (node (ref "R39") (pin "2") (pinfunction "2_2") (pintype "passive"))
      (node (ref "U1") (pin "10") (pinfunction "PA0-WKUP_10") (pintype "bidirectional"))
    )
    (net (code "18") (name "/LCD_SDA") (class "Default")
      (node (ref "JP11") (pin "4") (pinfunction "4_4") (pintype "passive"))
      (node (ref "R40") (pin "2") (pinfunction "2_2") (pintype "passive"))
      (node (ref "U1") (pin "11") (pinfunction "PA1_11") (pintype "bidirectional"))
    )
    (net (code "19") (name "/NRST") (class "Default")
      (node (ref "JP13") (pin "2") (pinfunction "2_2") (pintype "passive"))
      (node (ref "U1") (pin "7") (pinfunction "NRST_7") (pintype "bidirectional"))
    )
    (net (code "20") (name "/OUT_VOL") (class "Default")
      (node (ref "JP2") (pin "2") (pinfunction "2_2") (pintype "passive"))
      (node (ref "R2") (pin "2") (pinfunction "2_2") (pintype "passive"))
    )
    (net (code "21") (name "/RELAY_EN") (class "Default")
      (node (ref "C3") (pin "2") (pinfunction "2_2") (pintype "passive"))
      (node (ref "IC5") (pin "3") (pinfunction "E_3") (pintype "passive"))
      (node (ref "JP2") (pin "3") (pinfunction "3_3") (pintype "passive"))
      (node (ref "R9") (pin "2") (pinfunction "2_2") (pintype "passive"))
    )
    (net (code "22") (name "/RELAY_OUT") (class "Default")
      (node (ref "R7") (pin "2") (pinfunction "2_2") (pintype "passive"))
      (node (ref "U1") (pin "39") (pinfunction "PB3/JTDO_39") (pintype "bidirectional"))
    )
    (net (code "23") (name "/RFID_UNLOCK") (class "Default")
      (node (ref "C13") (pin "2") (pinfunction "2_2") (pintype "passive"))
      (node (ref "IC11") (pin "3") (pinfunction "E_3") (pintype "passive"))
      (node (ref "R18") (pin "2") (pinfunction "2_2") (pintype "passive"))
      (node (ref "U1") (pin "18") (pinfunction "PB0_18") (pintype "bidirectional"))
    )
    (net (code "24") (name "/SELA") (class "Default")
      (node (ref "C30") (pin "2") (pinfunction "2_2") (pintype "passive"))
      (node (ref "IC19") (pin "3") (pinfunction "E_3") (pintype "passive"))
      (node (ref "R45") (pin "2") (pinfunction "2_2") (pintype "passive"))
      (node (ref "U1") (pin "27") (pinfunction "PB14_27") (pintype "bidirectional"))
    )
    (net (code "25") (name "/SELB") (class "Default")
      (node (ref "C31") (pin "2") (pinfunction "2_2") (pintype "passive"))
      (node (ref "IC20") (pin "3") (pinfunction "E_3") (pintype "passive"))
      (node (ref "R48") (pin "2") (pinfunction "2_2") (pintype "passive"))
      (node (ref "U1") (pin "26") (pinfunction "PB13_26") (pintype "bidirectional"))
    )
    (net (code "26") (name "/ST_RXD") (class "Default")
      (node (ref "IC1") (pin "1") (pinfunction "RO_1") (pintype "output"))
      (node (ref "JP14") (pin "3") (pinfunction "3_3") (pintype "passive"))
      (node (ref "R1") (pin "1") (pinfunction "1_1") (pintype "passive"))
      (node (ref "U1") (pin "13") (pinfunction "PA3_13") (pintype "bidirectional"))
    )
    (net (code "27") (name "/ST_TXD") (class "Default")
      (node (ref "IC1") (pin "4") (pinfunction "DI_4") (pintype "input"))
      (node (ref "JP14") (pin "4") (pinfunction "4_4") (pintype "passive"))
      (node (ref "R6") (pin "1") (pinfunction "1_1") (pintype "passive"))
      (node (ref "U1") (pin "12") (pinfunction "PA2_12") (pintype "bidirectional"))
    )
    (net (code "28") (name "/SWCLK") (class "Default")
      (node (ref "JP13") (pin "3") (pinfunction "3_3") (pintype "passive"))
      (node (ref "U1") (pin "37") (pinfunction "PA14/JTCK/SWCLK_37") (pintype "bidirectional"))
    )
    (net (code "29") (name "/SWDIO") (class "Default")
      (node (ref "JP13") (pin "4") (pinfunction "4_4") (pintype "passive"))
      (node (ref "U1") (pin "34") (pinfunction "PA13/JTMS/SWDIO_34") (pintype "bidirectional"))
    )
    (net (code "30") (name "/UCK_LED") (class "Default")
      (node (ref "R19") (pin "2") (pinfunction "2_2") (pintype "passive"))
      (node (ref "U1") (pin "21") (pinfunction "PB10_21") (pintype "bidirectional"))
    )
    (net (code "31") (name "GND") (class "Default")
      (node (ref "*") (pin "0") (pinfunction "0_0") (pintype "passive"))
      (node (ref "*1") (pin "0") (pinfunction "0_0") (pintype "passive"))
      (node (ref "*2") (pin "0") (pinfunction "0_0") (pintype "passive"))
      (node (ref "*3") (pin "0") (pinfunction "0_0") (pintype "passive"))
      (node (ref "*5") (pin "0") (pinfunction "0_0") (pintype "passive"))
      (node (ref "C1") (pin "1") (pinfunction "1_1") (pintype "passive"))
      (node (ref "C10") (pin "2") (pinfunction "2_2") (pintype "passive"))
      (node (ref "C11") (pin "1") (pinfunction "1_1") (pintype "passive"))
      (node (ref "C12") (pin "1") (pinfunction "1_1") (pintype "passive"))
      (node (ref "C13") (pin "1") (pinfunction "1_1") (pintype "passive"))
      (node (ref "C14") (pin "2") (pinfunction "2_2") (pintype "passive"))
      (node (ref "C15") (pin "1") (pinfunction "1_1") (pintype "passive"))
      (node (ref "C16") (pin "1") (pinfunction "1_1") (pintype "passive"))
      (node (ref "C17") (pin "2") (pinfunction "2_2") (pintype "passive"))
      (node (ref "C18") (pin "1") (pinfunction "1_1") (pintype "passive"))
      (node (ref "C2") (pin "1") (pinfunction "1_1") (pintype "passive"))
      (node (ref "C20") (pin "1") (pinfunction "1_1") (pintype "passive"))
      (node (ref "C21") (pin "1") (pinfunction "1_1") (pintype "passive"))
      (node (ref "C22") (pin "1") (pinfunction "1_1") (pintype "passive"))
      (node (ref "C23") (pin "1") (pinfunction "1_1") (pintype "passive"))
      (node (ref "C24") (pin "2") (pinfunction "2_2") (pintype "passive"))
      (node (ref "C25") (pin "1") (pinfunction "1_1") (pintype "passive"))
      (node (ref "C26") (pin "1") (pinfunction "1_1") (pintype "passive"))
      (node (ref "C27") (pin "1") (pinfunction "1_1") (pintype "passive"))
      (node (ref "C28") (pin "1") (pinfunction "1_1") (pintype "passive"))
      (node (ref "C29") (pin "1") (pinfunction "1_1") (pintype "passive"))
      (node (ref "C3") (pin "1") (pinfunction "1_1") (pintype "passive"))
      (node (ref "C30") (pin "1") (pinfunction "1_1") (pintype "passive"))
      (node (ref "C31") (pin "1") (pinfunction "1_1") (pintype "passive"))
      (node (ref "C4") (pin "1") (pinfunction "1_1") (pintype "passive"))
      (node (ref "C5") (pin "1") (pinfunction "1_1") (pintype "passive"))
      (node (ref "C6") (pin "2") (pinfunction "2_2") (pintype "passive"))
      (node (ref "C7") (pin "2") (pinfunction "2_2") (pintype "passive"))
      (node (ref "C8") (pin "1") (pinfunction "1_1") (pintype "passive"))
      (node (ref "C9") (pin "1") (pinfunction "1_1") (pintype "passive"))
      (node (ref "DR1") (pin "2") (pinfunction "K_2") (pintype "passive"))
      (node (ref "IC1") (pin "5") (pinfunction "GND_5") (pintype "passive"))
      (node (ref "IC10") (pin "2") (pinfunction "K_2") (pintype "passive"))
      (node (ref "IC12") (pin "2") (pinfunction "K_2") (pintype "passive"))
      (node (ref "IC14") (pin "2") (pinfunction "K_2") (pintype "passive"))
      (node (ref "IC17") (pin "1") (pinfunction "GND_1") (pintype "passive"))
      (node (ref "IC2") (pin "2") (pinfunction "K_2") (pintype "passive"))
      (node (ref "IC3") (pin "5") (pinfunction "IN+_5") (pintype "input"))
      (node (ref "IC3") (pin "6") (pinfunction "IN-_6") (pintype "input"))
      (node (ref "IC4") (pin "3") (pinfunction "IN+_3") (pintype "input"))
      (node (ref "IC5") (pin "2") (pinfunction "K_2") (pintype "passive"))
      (node (ref "IC6") (pin "5") (pinfunction "IN+_5") (pintype "input"))
      (node (ref "IC6") (pin "6") (pinfunction "IN-_6") (pintype "input"))
      (node (ref "IC7") (pin "2") (pinfunction "K_2") (pintype "passive"))
      (node (ref "IC8") (pin "2") (pinfunction "K_2") (pintype "passive"))
      (node (ref "IC9") (pin "3") (pinfunction "K_3") (pintype "passive"))
      (node (ref "JP1") (pin "3") (pinfunction "3_3") (pintype "passive"))
      (node (ref "JP1") (pin "6") (pinfunction "6_6") (pintype "passive"))
      (node (ref "JP10") (pin "1") (pinfunction "1_1") (pintype "passive"))
      (node (ref "JP10") (pin "3") (pinfunction "3_3") (pintype "passive"))
      (node (ref "JP11") (pin "1") (pinfunction "1_1") (pintype "passive"))
      (node (ref "JP12") (pin "1") (pinfunction "1_1") (pintype "passive"))
      (node (ref "JP12") (pin "3") (pinfunction "3_3") (pintype "passive"))
      (node (ref "JP13") (pin "1") (pinfunction "1_1") (pintype "passive"))
      (node (ref "JP14") (pin "1") (pinfunction "1_1") (pintype "passive"))
      (node (ref "JP14") (pin "2") (pinfunction "2_2") (pintype "passive"))
      (node (ref "JP2") (pin "1") (pinfunction "1_1") (pintype "passive"))
      (node (ref "JP2") (pin "4") (pinfunction "4_4") (pintype "passive"))
      (node (ref "JP5") (pin "2") (pinfunction "2_2") (pintype "passive"))
      (node (ref "JP5") (pin "4") (pinfunction "4_4") (pintype "passive"))
      (node (ref "JP7") (pin "3") (pinfunction "3_3") (pintype "passive"))
      (node (ref "JP9") (pin "1") (pinfunction "1_1") (pintype "passive"))
      (node (ref "JP9") (pin "4") (pinfunction "4_4") (pintype "passive"))
      (node (ref "Q1") (pin "2") (pinfunction "S_2") (pintype "passive"))
      (node (ref "Q2") (pin "2") (pinfunction "S_2") (pintype "passive"))
      (node (ref "Q3") (pin "2") (pinfunction "S_2") (pintype "passive"))
      (node (ref "Q4") (pin "2") (pinfunction "S_2") (pintype "passive"))
      (node (ref "Q5") (pin "2") (pinfunction "S_2") (pintype "passive"))
      (node (ref "R11") (pin "1") (pinfunction "1_1") (pintype "passive"))
      (node (ref "R13") (pin "1") (pinfunction "1_1") (pintype "passive"))
      (node (ref "R17") (pin "1") (pinfunction "1_1") (pintype "passive"))
      (node (ref "R18") (pin "1") (pinfunction "1_1") (pintype "passive"))
      (node (ref "R22") (pin "1") (pinfunction "1_1") (pintype "passive"))
      (node (ref "R23") (pin "1") (pinfunction "1_1") (pintype "passive"))
      (node (ref "R27") (pin "1") (pinfunction "1_1") (pintype "passive"))
      (node (ref "R29") (pin "1") (pinfunction "1_1") (pintype "passive"))
      (node (ref "R34") (pin "1") (pinfunction "1_1") (pintype "passive"))
      (node (ref "R4") (pin "1") (pinfunction "1_1") (pintype "passive"))
      (node (ref "R41") (pin "1") (pinfunction "1_1") (pintype "passive"))
      (node (ref "R42") (pin "1") (pinfunction "1_1") (pintype "passive"))
      (node (ref "R45") (pin "1") (pinfunction "1_1") (pintype "passive"))
      (node (ref "R48") (pin "1") (pinfunction "1_1") (pintype "passive"))
      (node (ref "R8") (pin "1") (pinfunction "1_1") (pintype "passive"))
      (node (ref "R9") (pin "1") (pinfunction "1_1") (pintype "passive"))
      (node (ref "U1") (pin "23") (pinfunction "VSS_1_23") (pintype "power_in"))
      (node (ref "U1") (pin "35") (pinfunction "VSS_2_35") (pintype "power_in"))
      (node (ref "U1") (pin "44") (pinfunction "BOOT0_44") (pintype "input"))
      (node (ref "U1") (pin "47") (pinfunction "VSS_3_47") (pintype "power_in"))
      (node (ref "U1") (pin "8") (pinfunction "VSSA_8") (pintype "power_in"))
      (node (ref "V1") (pin "1") (pinfunction "GND_1") (pintype "passive"))
      (node (ref "VD1") (pin "1") (pinfunction "A_1") (pintype "passive"))
      (node (ref "VD2") (pin "1") (pinfunction "A_1") (pintype "passive"))
      (node (ref "VD4") (pin "1") (pinfunction "A_1") (pintype "passive"))
      (node (ref "X1") (pin "2") (pinfunction "2_2") (pintype "passive"))
      (node (ref "X1") (pin "4") (pinfunction "4_4") (pintype "passive"))
    )
    (net (code "32") (name "Net-(IC1-A)") (class "Default")
      (node (ref "IC1") (pin "6") (pinfunction "A_6") (pintype "passive"))
      (node (ref "J485R") (pin "1") (pinfunction "1_1") (pintype "passive"))
      (node (ref "R3") (pin "2") (pinfunction "2_2") (pintype "passive"))
      (node (ref "VD4") (pin "2") (pinfunction "K_2") (pintype "passive"))
    )
    (net (code "33") (name "Net-(IC1-B)") (class "Default")
      (node (ref "IC1") (pin "7") (pinfunction "B_7") (pintype "passive"))
      (node (ref "J485R") (pin "2") (pinfunction "2_2") (pintype "passive"))
      (node (ref "TP1") (pin "2") (pinfunction "2_2") (pintype "passive"))
      (node (ref "VD2") (pin "2") (pinfunction "K_2") (pintype "passive"))
    )
    (net (code "34") (name "Net-(IC2-A)") (class "Default")
      (node (ref "IC2") (pin "1") (pinfunction "A_1") (pintype "passive"))
      (node (ref "R2") (pin "1") (pinfunction "1_1") (pintype "passive"))
    )
    (net (code "35") (name "Net-(IC2-C)") (class "Default")
      (node (ref "IC2") (pin "4") (pinfunction "C_4") (pintype "passive"))
      (node (ref "R5") (pin "1") (pinfunction "1_1") (pintype "passive"))
    )
    (net (code "36") (name "Net-(IC3A-IN+)") (class "Default")
      (node (ref "C19") (pin "1") (pinfunction "1_1") (pintype "passive"))
      (node (ref "IC3") (pin "3") (pinfunction "IN+_3") (pintype "input"))
      (node (ref "IC4") (pin "1") (pinfunction "OUT_1") (pintype "output"))
      (node (ref "R28") (pin "1") (pinfunction "1_1") (pintype "passive"))
      (node (ref "R37") (pin "2") (pinfunction "2_2") (pintype "passive"))
      (node (ref "VD1") (pin "2") (pinfunction "K_2") (pintype "passive"))
    )
    (net (code "37") (name "Net-(IC3A-IN-)") (class "Default")
      (node (ref "IC3") (pin "2") (pinfunction "IN-_2") (pintype "input"))
      (node (ref "R31") (pin "2") (pinfunction "2_2") (pintype "passive"))
    )
    (net (code "38") (name "Net-(IC3A-OUT)") (class "Default")
      (node (ref "IC3") (pin "1") (pinfunction "OUT_1") (pintype "output"))
      (node (ref "R30") (pin "1") (pinfunction "1_1") (pintype "passive"))
    )
    (net (code "39") (name "Net-(IC4A-IN-)") (class "Default")
      (node (ref "C19") (pin "2") (pinfunction "2_2") (pintype "passive"))
      (node (ref "IC4") (pin "2") (pinfunction "IN-_2") (pintype "input"))
      (node (ref "R30") (pin "2") (pinfunction "2_2") (pintype "passive"))
      (node (ref "R37") (pin "1") (pinfunction "1_1") (pintype "passive"))
    )
    (net (code "40") (name "Net-(IC4B-IN+)") (class "Default")
      (node (ref "C17") (pin "1") (pinfunction "1_1") (pintype "passive"))
      (node (ref "IC4") (pin "5") (pinfunction "IN+_5") (pintype "input"))
      (node (ref "R28") (pin "2") (pinfunction "2_2") (pintype "passive"))
    )
    (net (code "41") (name "Net-(IC5-A)") (class "Default")
      (node (ref "IC5") (pin "1") (pinfunction "A_1") (pintype "passive"))
      (node (ref "R7") (pin "1") (pinfunction "1_1") (pintype "passive"))
    )
    (net (code "42") (name "Net-(IC6A-IN+)") (class "Default")
      (node (ref "IC6") (pin "3") (pinfunction "IN+_3") (pintype "input"))
      (node (ref "R38") (pin "1") (pinfunction "1_1") (pintype "passive"))
      (node (ref "R42") (pin "2") (pinfunction "2_2") (pintype "passive"))
    )
    (net (code "43") (name "Net-(IC6A-IN-)") (class "Default")
      (node (ref "IC6") (pin "1") (pinfunction "OUT_1") (pintype "output"))
      (node (ref "IC6") (pin "2") (pinfunction "IN-_2") (pintype "input"))
      (node (ref "R31") (pin "1") (pinfunction "1_1") (pintype "passive"))
    )
    (net (code "44") (name "Net-(IC7-A)") (class "Default")
      (node (ref "IC7") (pin "1") (pinfunction "A_1") (pintype "passive"))
      (node (ref "R10") (pin "1") (pinfunction "1_1") (pintype "passive"))
    )
    (net (code "45") (name "Net-(IC7-E)") (class "Default")
      (node (ref "C4") (pin "2") (pinfunction "2_2") (pintype "passive"))
      (node (ref "IC7") (pin "3") (pinfunction "E_3") (pintype "passive"))
      (node (ref "Q1") (pin "1") (pinfunction "G_1") (pintype "passive"))
      (node (ref "R11") (pin "2") (pinfunction "2_2") (pintype "passive"))
    )
    (net (code "46") (name "Net-(IC8-A)") (class "Default")
      (node (ref "IC8") (pin "1") (pinfunction "A_1") (pintype "passive"))
      (node (ref "R12") (pin "1") (pinfunction "1_1") (pintype "passive"))
    )
    (net (code "47") (name "Net-(IC8-E)") (class "Default")
      (node (ref "C9") (pin "2") (pinfunction "2_2") (pintype "passive"))
      (node (ref "IC8") (pin "3") (pinfunction "E_3") (pintype "passive"))
      (node (ref "Q2") (pin "1") (pinfunction "G_1") (pintype "passive"))
      (node (ref "R13") (pin "2") (pinfunction "2_2") (pintype "passive"))
    )
    (net (code "48") (name "Net-(IC9-A)") (class "Default")
      (node (ref "IC9") (pin "1") (pinfunction "A_1") (pintype "passive"))
      (node (ref "R52") (pin "2") (pinfunction "2_2") (pintype "passive"))
    )
    (net (code "49") (name "Net-(IC9-OUT)") (class "Default")
      (node (ref "IC9") (pin "5") (pinfunction "OUT_5") (pintype "passive"))
      (node (ref "R54") (pin "2") (pinfunction "2_2") (pintype "passive"))
    )
    (net (code "50") (name "Net-(IC10-A)") (class "Default")
      (node (ref "IC10") (pin "1") (pinfunction "A_1") (pintype "passive"))
      (node (ref "R15") (pin "1") (pinfunction "1_1") (pintype "passive"))
    )
    (net (code "51") (name "Net-(IC10-E)") (class "Default")
      (node (ref "C12") (pin "2") (pinfunction "2_2") (pintype "passive"))
      (node (ref "IC10") (pin "3") (pinfunction "E_3") (pintype "passive"))
      (node (ref "Q3") (pin "1") (pinfunction "G_1") (pintype "passive"))
      (node (ref "R17") (pin "2") (pinfunction "2_2") (pintype "passive"))
    )
    (net (code "52") (name "Net-(IC11-A)") (class "Default")
      (node (ref "IC11") (pin "1") (pinfunction "A_1") (pintype "passive"))
      (node (ref "R16") (pin "1") (pinfunction "1_1") (pintype "passive"))
    )
    (net (code "53") (name "Net-(IC11-C)") (class "Default")
      (node (ref "IC11") (pin "4") (pinfunction "C_4") (pintype "passive"))
      (node (ref "R14") (pin "1") (pinfunction "1_1") (pintype "passive"))
    )
    (net (code "54") (name "Net-(IC11-K)") (class "Default")
      (node (ref "IC11") (pin "2") (pinfunction "K_2") (pintype "passive"))
      (node (ref "JP5") (pin "3") (pinfunction "3_3") (pintype "passive"))
    )
    (net (code "55") (name "Net-(IC12-A)") (class "Default")
      (node (ref "IC12") (pin "1") (pinfunction "A_1") (pintype "passive"))
      (node (ref "R19") (pin "1") (pinfunction "1_1") (pintype "passive"))
    )
    (net (code "56") (name "Net-(IC12-E)") (class "Default")
      (node (ref "C16") (pin "2") (pinfunction "2_2") (pintype "passive"))
      (node (ref "IC12") (pin "3") (pinfunction "E_3") (pintype "passive"))
      (node (ref "Q4") (pin "1") (pinfunction "G_1") (pintype "passive"))
      (node (ref "R22") (pin "2") (pinfunction "2_2") (pintype "passive"))
    )
    (net (code "57") (name "Net-(IC13-A)") (class "Default")
      (node (ref "IC13") (pin "1") (pinfunction "A_1") (pintype "passive"))
      (node (ref "R21") (pin "1") (pinfunction "1_1") (pintype "passive"))
    )
    (net (code "58") (name "Net-(IC13-C)") (class "Default")
      (node (ref "IC13") (pin "4") (pinfunction "C_4") (pintype "passive"))
      (node (ref "R20") (pin "1") (pinfunction "1_1") (pintype "passive"))
    )
    (net (code "59") (name "Net-(IC13-K)") (class "Default")
      (node (ref "IC13") (pin "2") (pinfunction "K_2") (pintype "passive"))
      (node (ref "JP7") (pin "2") (pinfunction "2_2") (pintype "passive"))
    )
    (net (code "60") (name "Net-(IC14-A)") (class "Default")
      (node (ref "IC14") (pin "1") (pinfunction "A_1") (pintype "passive"))
      (node (ref "R24") (pin "1") (pinfunction "1_1") (pintype "passive"))
    )
    (net (code "61") (name "Net-(IC14-E)") (class "Default")
      (node (ref "C26") (pin "2") (pinfunction "2_2") (pintype "passive"))
      (node (ref "IC14") (pin "3") (pinfunction "E_3") (pintype "passive"))
      (node (ref "Q5") (pin "1") (pinfunction "G_1") (pintype "passive"))
      (node (ref "R27") (pin "2") (pinfunction "2_2") (pintype "passive"))
    )
    (net (code "62") (name "Net-(IC15-A)") (class "Default")
      (node (ref "IC15") (pin "1") (pinfunction "A_1") (pintype "passive"))
      (node (ref "R26") (pin "1") (pinfunction "1_1") (pintype "passive"))
    )
    (net (code "63") (name "Net-(IC15-C)") (class "Default")
      (node (ref "IC15") (pin "4") (pinfunction "C_4") (pintype "passive"))
      (node (ref "R25") (pin "1") (pinfunction "1_1") (pintype "passive"))
    )
    (net (code "64") (name "Net-(IC15-K)") (class "Default")
      (node (ref "IC15") (pin "2") (pinfunction "K_2") (pintype "passive"))
      (node (ref "JP7") (pin "1") (pinfunction "1_1") (pintype "passive"))
    )
    (net (code "65") (name "Net-(IC16-A)") (class "Default")
      (node (ref "IC16") (pin "1") (pinfunction "A_1") (pintype "passive"))
      (node (ref "R33") (pin "1") (pinfunction "1_1") (pintype "passive"))
    )
    (net (code "66") (name "Net-(IC16-C)") (class "Default")
      (node (ref "IC16") (pin "4") (pinfunction "C_4") (pintype "passive"))
      (node (ref "R32") (pin "1") (pinfunction "1_1") (pintype "passive"))
    )
    (net (code "67") (name "Net-(IC16-K)") (class "Default")
      (node (ref "IC16") (pin "2") (pinfunction "K_2") (pintype "passive"))
      (node (ref "JP10") (pin "4") (pinfunction "4_4") (pintype "passive"))
    )
    (net (code "68") (name "Net-(IC18-A)") (class "Default")
      (node (ref "IC18") (pin "1") (pinfunction "A_1") (pintype "passive"))
      (node (ref "R36") (pin "1") (pinfunction "1_1") (pintype "passive"))
    )
    (net (code "69") (name "Net-(IC18-C)") (class "Default")
      (node (ref "IC18") (pin "4") (pinfunction "C_4") (pintype "passive"))
      (node (ref "R35") (pin "1") (pinfunction "1_1") (pintype "passive"))
    )
    (net (code "70") (name "Net-(IC18-K)") (class "Default")
      (node (ref "IC18") (pin "2") (pinfunction "K_2") (pintype "passive"))
      (node (ref "JP10") (pin "2") (pinfunction "2_2") (pintype "passive"))
    )
    (net (code "71") (name "Net-(IC19-A)") (class "Default")
      (node (ref "IC19") (pin "1") (pinfunction "A_1") (pintype "passive"))
      (node (ref "R44") (pin "1") (pinfunction "1_1") (pintype "passive"))
    )
    (net (code "72") (name "Net-(IC19-C)") (class "Default")
      (node (ref "IC19") (pin "4") (pinfunction "C_4") (pintype "passive"))
      (node (ref "R43") (pin "1") (pinfunction "1_1") (pintype "passive"))
    )
    (net (code "73") (name "Net-(IC19-K)") (class "Default")
      (node (ref "IC19") (pin "2") (pinfunction "K_2") (pintype "passive"))
      (node (ref "JP12") (pin "4") (pinfunction "4_4") (pintype "passive"))
    )
    (net (code "74") (name "Net-(IC20-A)") (class "Default")
      (node (ref "IC20") (pin "1") (pinfunction "A_1") (pintype "passive"))
      (node (ref "R47") (pin "1") (pinfunction "1_1") (pintype "passive"))
    )
    (net (code "75") (name "Net-(IC20-C)") (class "Default")
      (node (ref "IC20") (pin "4") (pinfunction "C_4") (pintype "passive"))
      (node (ref "R46") (pin "1") (pinfunction "1_1") (pintype "passive"))
    )
    (net (code "76") (name "Net-(IC20-K)") (class "Default")
      (node (ref "IC20") (pin "2") (pinfunction "K_2") (pintype "passive"))
      (node (ref "JP12") (pin "2") (pinfunction "2_2") (pintype "passive"))
    )
    (net (code "77") (name "Net-(Q1-D)") (class "Default")
      (node (ref "JP3") (pin "2") (pinfunction "2_2") (pintype "passive"))
      (node (ref "Q1") (pin "3") (pinfunction "D_3") (pintype "passive"))
    )
    (net (code "78") (name "Net-(Q2-D)") (class "Default")
      (node (ref "JP3") (pin "4") (pinfunction "4_4") (pintype "passive"))
      (node (ref "Q2") (pin "3") (pinfunction "D_3") (pintype "passive"))
    )
    (net (code "79") (name "Net-(Q3-D)") (class "Default")
      (node (ref "JP6") (pin "2") (pinfunction "2_2") (pintype "passive"))
      (node (ref "Q3") (pin "3") (pinfunction "D_3") (pintype "passive"))
    )
    (net (code "80") (name "Net-(Q4-D)") (class "Default")
      (node (ref "JP6") (pin "4") (pinfunction "4_4") (pintype "passive"))
      (node (ref "Q4") (pin "3") (pinfunction "D_3") (pintype "passive"))
    )
    (net (code "81") (name "Net-(Q5-D)") (class "Default")
      (node (ref "JP8") (pin "1") (pinfunction "1_1") (pintype "passive"))
      (node (ref "Q5") (pin "3") (pinfunction "D_3") (pintype "passive"))
    )
    (net (code "82") (name "Net-(R3-Pad1)") (class "Default")
      (node (ref "R3") (pin "1") (pinfunction "1_1") (pintype "passive"))
      (node (ref "TP1") (pin "1") (pinfunction "1_1") (pintype "passive"))
    )
    (net (code "83") (name "Net-(U1-OSC_IN{slash}PD0)") (class "Default")
      (node (ref "C10") (pin "1") (pinfunction "1_1") (pintype "passive"))
      (node (ref "U1") (pin "5") (pinfunction "OSC_IN/PD0_5") (pintype "input"))
      (node (ref "X1") (pin "1") (pinfunction "1_1") (pintype "passive"))
    )
    (net (code "84") (name "Net-(U1-OSC_OUT{slash}PD1)") (class "Default")
      (node (ref "C14") (pin "1") (pinfunction "1_1") (pintype "passive"))
      (node (ref "U1") (pin "6") (pinfunction "OSC_OUT/PD1_6") (pintype "output"))
      (node (ref "X1") (pin "3") (pinfunction "3_3") (pintype "passive"))
    )
    (net (code "85") (name "Net-(U1-PC14-OSC32_IN)") (class "Default")
      (node (ref "C11") (pin "2") (pinfunction "2_2") (pintype "passive"))
      (node (ref "U1") (pin "3") (pinfunction "PC14-OSC32_IN_3") (pintype "bidirectional"))
      (node (ref "X2") (pin "2") (pinfunction "2_2") (pintype "passive"))
    )
    (net (code "86") (name "Net-(U1-PC15-OSC32_OUT)") (class "Default")
      (node (ref "C15") (pin "2") (pinfunction "2_2") (pintype "passive"))
      (node (ref "U1") (pin "4") (pinfunction "PC15-OSC32_OUT_4") (pintype "bidirectional"))
      (node (ref "X2") (pin "1") (pinfunction "1_1") (pintype "passive"))
    )
    (net (code "87") (name "Net-(VD3-K)") (class "Default")
      (node (ref "R38") (pin "2") (pinfunction "2_2") (pintype "passive"))
      (node (ref "VD3") (pin "2") (pinfunction "K_2") (pintype "passive"))
    )
    (net (code "88") (name "VCC-5V") (class "Default")
      (node (ref "IC3") (pin "4") (pinfunction "V-_4") (pintype "power_in"))
      (node (ref "IC4") (pin "4") (pinfunction "V-_4") (pintype "power_in"))
      (node (ref "IC6") (pin "4") (pinfunction "V-_4") (pintype "power_in"))
      (node (ref "JP1") (pin "5") (pinfunction "5_5") (pintype "passive"))
    )
    (net (code "89") (name "VCC-12V") (class "Default")
      (node (ref "IC9") (pin "4") (pinfunction "VSS_4") (pintype "passive"))
      (node (ref "JP1") (pin "4") (pinfunction "4_4") (pintype "passive"))
    )
    (net (code "90") (name "VCC3V3") (class "Default")
      (node (ref "C1") (pin "2") (pinfunction "2_2") (pintype "passive"))
      (node (ref "C18") (pin "2") (pinfunction "2_2") (pintype "passive"))
      (node (ref "C20") (pin "2") (pinfunction "2_2") (pintype "passive"))
      (node (ref "C21") (pin "2") (pinfunction "2_2") (pintype "passive"))
      (node (ref "C22") (pin "2") (pinfunction "2_2") (pintype "passive"))
      (node (ref "C24") (pin "1") (pinfunction "1_1") (pintype "passive"))
      (node (ref "C7") (pin "1") (pinfunction "1_1") (pintype "passive"))
      (node (ref "C8") (pin "2") (pinfunction "2_2") (pintype "passive"))
      (node (ref "IC1") (pin "8") (pinfunction "VCC_8") (pintype "passive"))
      (node (ref "IC17") (pin "3") (pinfunction "VDD_3") (pintype "passive"))
      (node (ref "JP11") (pin "2") (pinfunction "2_2") (pintype "passive"))
      (node (ref "JP9") (pin "3") (pinfunction "3_3") (pintype "passive"))
      (node (ref "R1") (pin "2") (pinfunction "2_2") (pintype "passive"))
      (node (ref "R14") (pin "2") (pinfunction "2_2") (pintype "passive"))
      (node (ref "R20") (pin "2") (pinfunction "2_2") (pintype "passive"))
      (node (ref "R25") (pin "2") (pinfunction "2_2") (pintype "passive"))
      (node (ref "R32") (pin "2") (pinfunction "2_2") (pintype "passive"))
      (node (ref "R35") (pin "2") (pinfunction "2_2") (pintype "passive"))
      (node (ref "R39") (pin "1") (pinfunction "1_1") (pintype "passive"))
      (node (ref "R40") (pin "1") (pinfunction "1_1") (pintype "passive"))
      (node (ref "R43") (pin "2") (pinfunction "2_2") (pintype "passive"))
      (node (ref "R46") (pin "2") (pinfunction "2_2") (pintype "passive"))
      (node (ref "R5") (pin "2") (pinfunction "2_2") (pintype "passive"))
      (node (ref "R6") (pin "2") (pinfunction "2_2") (pintype "passive"))
      (node (ref "U1") (pin "24") (pinfunction "VDD_1_24") (pintype "power_in"))
      (node (ref "U1") (pin "36") (pinfunction "VDD_2_36") (pintype "power_in"))
      (node (ref "U1") (pin "48") (pinfunction "VDD_3_48") (pintype "power_in"))
      (node (ref "U1") (pin "9") (pinfunction "VDDA_9") (pintype "power_in"))
      (node (ref "V1") (pin "2") (pinfunction "Vout_2") (pintype "passive"))
    )
    (net (code "91") (name "VCC5V") (class "Default")
      (node (ref "C5") (pin "2") (pinfunction "2_2") (pintype "passive"))
      (node (ref "C6") (pin "1") (pinfunction "1_1") (pintype "passive"))
      (node (ref "IC3") (pin "8") (pinfunction "V+_8") (pintype "power_in"))
      (node (ref "IC4") (pin "8") (pinfunction "V+_8") (pintype "power_in"))
      (node (ref "IC6") (pin "8") (pinfunction "V+_8") (pintype "power_in"))
      (node (ref "JP1") (pin "2") (pinfunction "2_2") (pintype "passive"))
      (node (ref "V1") (pin "3") (pinfunction "Vin_3") (pintype "passive"))
    )
    (net (code "92") (name "VCC12V") (class "Default")
      (node (ref "IC10") (pin "4") (pinfunction "C_4") (pintype "passive"))
      (node (ref "IC12") (pin "4") (pinfunction "C_4") (pintype "passive"))
      (node (ref "IC14") (pin "4") (pinfunction "C_4") (pintype "passive"))
      (node (ref "IC5") (pin "4") (pinfunction "C_4") (pintype "passive"))
      (node (ref "IC7") (pin "4") (pinfunction "C_4") (pintype "passive"))
      (node (ref "IC8") (pin "4") (pinfunction "C_4") (pintype "passive"))
      (node (ref "IC9") (pin "6") (pinfunction "VDD_6") (pintype "passive"))
      (node (ref "JP1") (pin "1") (pinfunction "1_1") (pintype "passive"))
      (node (ref "JP3") (pin "1") (pinfunction "1_1") (pintype "passive"))
      (node (ref "JP3") (pin "3") (pinfunction "3_3") (pintype "passive"))
      (node (ref "JP5") (pin "1") (pinfunction "1_1") (pintype "passive"))
      (node (ref "JP6") (pin "1") (pinfunction "1_1") (pintype "passive"))
      (node (ref "JP6") (pin "3") (pinfunction "3_3") (pintype "passive"))
      (node (ref "JP7") (pin "4") (pinfunction "4_4") (pintype "passive"))
      (node (ref "JP8") (pin "2") (pinfunction "2_2") (pintype "passive"))
      (node (ref "R16") (pin "2") (pinfunction "2_2") (pintype "passive"))
      (node (ref "R21") (pin "2") (pinfunction "2_2") (pintype "passive"))
      (node (ref "R26") (pin "2") (pinfunction "2_2") (pintype "passive"))
      (node (ref "R33") (pin "2") (pinfunction "2_2") (pintype "passive"))
      (node (ref "R36") (pin "2") (pinfunction "2_2") (pintype "passive"))
      (node (ref "R44") (pin "2") (pinfunction "2_2") (pintype "passive"))
      (node (ref "R47") (pin "2") (pinfunction "2_2") (pintype "passive"))
    )
    (net (code "93") (name "unconnected-(IC3B-OUT-Pad7)") (class "Default")
      (node (ref "IC3") (pin "7") (pinfunction "OUT_7") (pintype "output+no_connect"))
    )
    (net (code "94") (name "unconnected-(IC6B-OUT-Pad7)") (class "Default")
      (node (ref "IC6") (pin "7") (pinfunction "OUT_7") (pintype "output+no_connect"))
    )
    (net (code "95") (name "unconnected-(IC9-NC-Pad2)") (class "Default")
      (node (ref "IC9") (pin "2") (pinfunction "NC_2") (pintype "passive"))
    )
    (net (code "96") (name "unconnected-(U1-PA11-Pad32)") (class "Default")
      (node (ref "U1") (pin "32") (pinfunction "PA11_32") (pintype "bidirectional"))
    )
    (net (code "97") (name "unconnected-(U1-PA12-Pad33)") (class "Default")
      (node (ref "U1") (pin "33") (pinfunction "PA12_33") (pintype "bidirectional"))
    )
    (net (code "98") (name "unconnected-(U1-PB5-Pad41)") (class "Default")
      (node (ref "U1") (pin "41") (pinfunction "PB5_41") (pintype "bidirectional"))
    )
    (net (code "99") (name "unconnected-(U1-PB6-Pad42)") (class "Default")
      (node (ref "U1") (pin "42") (pinfunction "PB6_42") (pintype "bidirectional"))
    )
    (net (code "100") (name "unconnected-(U1-PB7-Pad43)") (class "Default")
      (node (ref "U1") (pin "43") (pinfunction "PB7_43") (pintype "bidirectional"))
    )
    (net (code "101") (name "unconnected-(U1-PB8-Pad45)") (class "Default")
      (node (ref "U1") (pin "45") (pinfunction "PB8_45") (pintype "bidirectional"))
    )
    (net (code "102") (name "unconnected-(U1-PB9-Pad46)") (class "Default")
      (node (ref "U1") (pin "46") (pinfunction "PB9_46") (pintype "bidirectional"))
    )
    (net (code "103") (name "unconnected-(U1-PC13-TAMPER-RTC-Pad2)") (class "Default")
      (node (ref "U1") (pin "2") (pinfunction "PC13-TAMPER-RTC_2") (pintype "bidirectional"))
    )
    (net (code "104") (name "unconnected-(U1-VBAT-Pad1)") (class "Default")
      (node (ref "U1") (pin "1") (pinfunction "VBAT_1") (pintype "power_in+no_connect"))
    )
  )
)
